# eagle_1_board.net
KiCad netlist of a schematic drawn in EAGLE
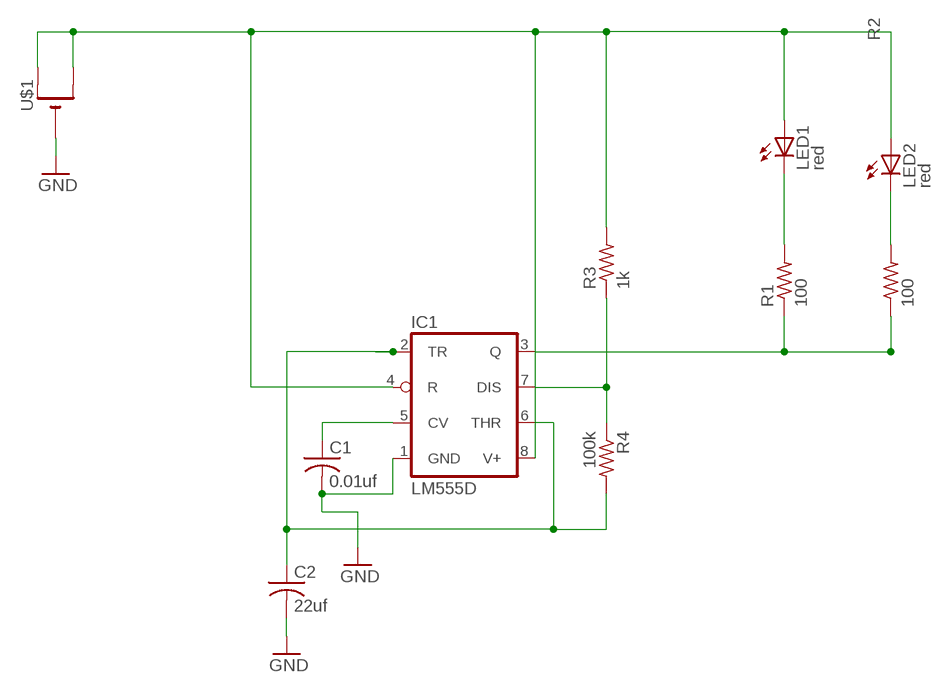
[diagram p0: schematic, sheet 1]

(export (version "E")
  (design (tool "Eeschema 10.0.6"))
  (components
    (comp (ref "C1")
      (value "0.01uf")
      (footprint "eagle-import:C0805")
      (libsource (lib "eagle-import") (part "C-USC0805"))
    )
    (comp (ref "C2")
      (value "22uf")
      (footprint "eagle-import:C0805")
      (libsource (lib "eagle-import") (part "C-USC0805"))
    )
    (comp (ref "IC1")
      (value "LM555D")
      (footprint "eagle-import:SO08")
      (libsource (lib "eagle-import") (part "555DLM"))
    )
    (comp (ref "LED1")
      (value "red")
      (footprint "eagle-import:CHIPLED_0805")
      (libsource (lib "eagle-import") (part "LEDCHIPLED_0805"))
    )
    (comp (ref "LED2")
      (value "red")
      (footprint "eagle-import:CHIPLED_0805")
      (libsource (lib "eagle-import") (part "LEDCHIPLED_0805"))
    )
    (comp (ref "R1")
      (value "100")
      (footprint "eagle-import:R0805")
      (libsource (lib "eagle-import") (part "R-US_R0805"))
    )
    (comp (ref "R2")
      (value "100")
      (footprint "eagle-import:R0805")
      (libsource (lib "eagle-import") (part "R-US_R0805"))
    )
    (comp (ref "R3")
      (value "1k")
      (footprint "eagle-import:R0805")
      (libsource (lib "eagle-import") (part "R-US_R0805"))
    )
    (comp (ref "R4")
      (value "100k")
      (footprint "eagle-import:R0805")
      (libsource (lib "eagle-import") (part "R-US_R0805"))
    )
    (comp (ref "U$1")
      (value "CR1220SMT")
      (footprint "eagle-import:CR1220-SMD")
      (libsource (lib "eagle-import") (part "CR1220SMT"))
    )
  )
  (nets
    (net (code "1") (name "GND") (class "Default")
      (node (ref "C1") (pin "2") (pinfunction "2_2") (pintype "passive"))
      (node (ref "C2") (pin "2") (pinfunction "2_2") (pintype "passive"))
      (node (ref "IC1") (pin "1") (pinfunction "GND_1") (pintype "power_in"))
      (node (ref "U$1") (pin "-") (pinfunction "-_-") (pintype "passive"))
    )
    (net (code "2") (name "Net-(IC1-CV)") (class "Default")
      (node (ref "C1") (pin "1") (pinfunction "1_1") (pintype "passive"))
      (node (ref "IC1") (pin "5") (pinfunction "CV_5") (pintype "input"))
    )
    (net (code "3") (name "Net-(IC1-DIS)") (class "Default")
      (node (ref "IC1") (pin "7") (pinfunction "DIS_7") (pintype "input"))
      (node (ref "R3") (pin "1") (pinfunction "1_1") (pintype "passive"))
      (node (ref "R4") (pin "1") (pinfunction "1_1") (pintype "passive"))
    )
    (net (code "4") (name "Net-(IC1-Q)") (class "Default")
      (node (ref "IC1") (pin "3") (pinfunction "Q_3") (pintype "output"))
      (node (ref "R1") (pin "1") (pinfunction "1_1") (pintype "passive"))
      (node (ref "R2") (pin "1") (pinfunction "1_1") (pintype "passive"))
    )
    (net (code "5") (name "Net-(IC1-R)") (class "Default")
      (node (ref "IC1") (pin "4") (pinfunction "R_4") (pintype "input"))
      (node (ref "IC1") (pin "8") (pinfunction "V+_8") (pintype "power_in"))
      (node (ref "LED1") (pin "A") (pinfunction "A_A") (pintype "passive"))
      (node (ref "LED2") (pin "A") (pinfunction "A_A") (pintype "passive"))
      (node (ref "R3") (pin "2") (pinfunction "2_2") (pintype "passive"))
      (node (ref "U$1") (pin "+$1") (pinfunction "+_+$1") (pintype "passive"))
      (node (ref "U$1") (pin "+$2") (pinfunction "+1_+$2") (pintype "passive"))
    )
    (net (code "6") (name "Net-(IC1-THR)") (class "Default")
      (node (ref "C2") (pin "1") (pinfunction "1_1") (pintype "passive"))
      (node (ref "IC1") (pin "2") (pinfunction "TR_2") (pintype "input"))
      (node (ref "IC1") (pin "6") (pinfunction "THR_6") (pintype "input"))
      (node (ref "R4") (pin "2") (pinfunction "2_2") (pintype "passive"))
    )
    (net (code "7") (name "Net-(LED1-PadC)") (class "Default")
      (node (ref "LED1") (pin "C") (pinfunction "C_C") (pintype "passive"))
      (node (ref "R1") (pin "2") (pinfunction "2_2") (pintype "passive"))
    )
    (net (code "8") (name "Net-(LED2-PadC)") (class "Default")
      (node (ref "LED2") (pin "C") (pinfunction "C_C") (pintype "passive"))
      (node (ref "R2") (pin "2") (pinfunction "2_2") (pintype "passive"))
    )
  )
)
